# SH1_-_CONNECTORS.net
KiCad netlist of a schematic drawn in Altium Designer
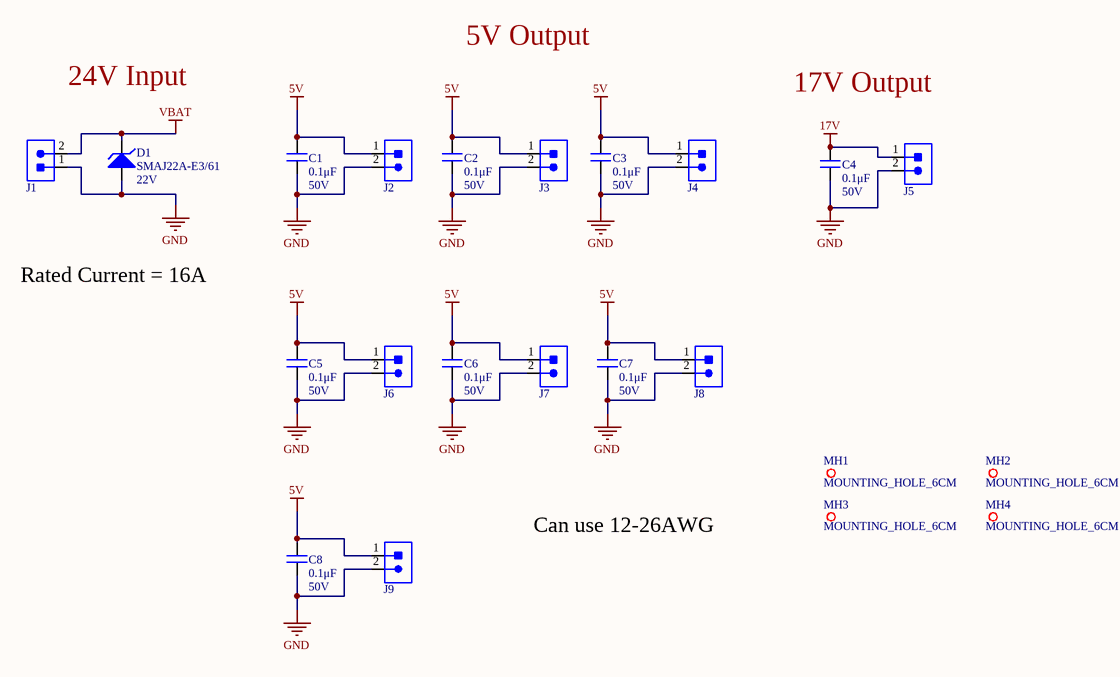
[diagram p0: SH1 - CONNECTORS.SchDoc]

(export (version "E")
  (design (tool "Eeschema 10.0.6"))
  (components
    (comp (ref "C1")
      (value "0.1μF")
      (footprint "CAPC2012X140N")
      (description "CAP CER 0.1UF 50V X7R 0805")
      (fields (field (name "TOLERANCE") "10%") (field (name "VOLTAGE RATING") "50V"))
      (libsource (lib "UWRT_Schematic_Library_2020") (part "CAP_0.1uF_50V_0805"))
    )
    (comp (ref "C2")
      (value "0.1μF")
      (footprint "CAPC2012X140N")
      (description "CAP CER 0.1UF 50V X7R 0805")
      (fields (field (name "TOLERANCE") "10%") (field (name "VOLTAGE RATING") "50V"))
      (libsource (lib "UWRT_Schematic_Library_2020") (part "CAP_0.1uF_50V_0805"))
    )
    (comp (ref "C3")
      (value "0.1μF")
      (footprint "CAPC2012X140N")
      (description "CAP CER 0.1UF 50V X7R 0805")
      (fields (field (name "TOLERANCE") "10%") (field (name "VOLTAGE RATING") "50V"))
      (libsource (lib "UWRT_Schematic_Library_2020") (part "CAP_0.1uF_50V_0805"))
    )
    (comp (ref "C4")
      (value "0.1μF")
      (footprint "CAPC2012X140N")
      (description "CAP CER 0.1UF 50V X7R 0805")
      (fields (field (name "TOLERANCE") "10%") (field (name "VOLTAGE RATING") "50V"))
      (libsource (lib "UWRT_Schematic_Library_2020") (part "CAP_0.1uF_50V_0805"))
    )
    (comp (ref "C5")
      (value "0.1μF")
      (footprint "CAPC2012X140N")
      (description "CAP CER 0.1UF 50V X7R 0805")
      (fields (field (name "TOLERANCE") "10%") (field (name "VOLTAGE RATING") "50V"))
      (libsource (lib "UWRT_Schematic_Library_2020") (part "CAP_0.1uF_50V_0805"))
    )
    (comp (ref "C6")
      (value "0.1μF")
      (footprint "CAPC2012X140N")
      (description "CAP CER 0.1UF 50V X7R 0805")
      (fields (field (name "TOLERANCE") "10%") (field (name "VOLTAGE RATING") "50V"))
      (libsource (lib "UWRT_Schematic_Library_2020") (part "CAP_0.1uF_50V_0805"))
    )
    (comp (ref "C7")
      (value "0.1μF")
      (footprint "CAPC2012X140N")
      (description "CAP CER 0.1UF 50V X7R 0805")
      (fields (field (name "TOLERANCE") "10%") (field (name "VOLTAGE RATING") "50V"))
      (libsource (lib "UWRT_Schematic_Library_2020") (part "CAP_0.1uF_50V_0805"))
    )
    (comp (ref "C8")
      (value "0.1μF")
      (footprint "CAPC2012X140N")
      (description "CAP CER 0.1UF 50V X7R 0805")
      (fields (field (name "TOLERANCE") "10%") (field (name "VOLTAGE RATING") "50V"))
      (libsource (lib "UWRT_Schematic_Library_2020") (part "CAP_0.1uF_50V_0805"))
    )
    (comp (ref "D1")
      (value "SMAJ22A-E3/61")
      (footprint "DO-214AC_UNI")
      (description "TVS DIODE 22V 35.5VC SMA")
      (fields
        (field (name "VOLTAGE") "22V")
        (field (name "MANUFACTURER PART NUMBER 1") "SMAJ22A-E3/61")
        (field (name "REVERSE STANDOFF VOLTAGE") "22V")
      )
      (libsource (lib "UWRT_Schematic_Library_2020") (part "SMAJ22A-E3/61"))
    )
    (comp (ref "J1")
      (value "1935161")
      (footprint "1935161")
      (description "TERM BLK 2POS SIDE ENTRY 5MM")
      (fields (field (name "VOLTAGE") "300V"))
      (libsource (lib "") (part "CON_2M_TERM_1"))
    )
    (comp (ref "J2")
      (value "1935161")
      (footprint "1935161")
      (description "TERM BLK 2POS SIDE ENTRY 5MM")
      (fields (field (name "VOLTAGE") "300V"))
      (libsource (lib "UWRT_Schematic_Library_2020") (part "CON_2M_TERM"))
    )
    (comp (ref "J3")
      (value "1935161")
      (footprint "1935161")
      (description "TERM BLK 2POS SIDE ENTRY 5MM")
      (fields (field (name "VOLTAGE") "300V"))
      (libsource (lib "UWRT_Schematic_Library_2020") (part "CON_2M_TERM"))
    )
    (comp (ref "J4")
      (value "1935161")
      (footprint "1935161")
      (description "TERM BLK 2POS SIDE ENTRY 5MM")
      (fields (field (name "VOLTAGE") "300V"))
      (libsource (lib "UWRT_Schematic_Library_2020") (part "CON_2M_TERM"))
    )
    (comp (ref "J5")
      (value "1935161")
      (footprint "1935161")
      (description "TERM BLK 2POS SIDE ENTRY 5MM")
      (fields (field (name "VOLTAGE") "300V"))
      (libsource (lib "UWRT_Schematic_Library_2020") (part "CON_2M_TERM"))
    )
    (comp (ref "J6")
      (value "1935161")
      (footprint "1935161")
      (description "TERM BLK 2POS SIDE ENTRY 5MM")
      (fields (field (name "VOLTAGE") "300V"))
      (libsource (lib "UWRT_Schematic_Library_2020") (part "CON_2M_TERM"))
    )
    (comp (ref "J7")
      (value "1935161")
      (footprint "1935161")
      (description "TERM BLK 2POS SIDE ENTRY 5MM")
      (fields (field (name "VOLTAGE") "300V"))
      (libsource (lib "UWRT_Schematic_Library_2020") (part "CON_2M_TERM"))
    )
    (comp (ref "J8")
      (value "1935161")
      (footprint "1935161")
      (description "TERM BLK 2POS SIDE ENTRY 5MM")
      (fields (field (name "VOLTAGE") "300V"))
      (libsource (lib "UWRT_Schematic_Library_2020") (part "CON_2M_TERM"))
    )
    (comp (ref "J9")
      (value "1935161")
      (footprint "1935161")
      (description "TERM BLK 2POS SIDE ENTRY 5MM")
      (fields (field (name "VOLTAGE") "300V"))
      (libsource (lib "UWRT_Schematic_Library_2020") (part "CON_2M_TERM"))
    )
    (comp (ref "MH1")
      (value "MOUNTING_HOLE_6CM")
      (footprint "MOUNTING_HOLE")
      (libsource (lib "UWRT_Schematic_Library_2020") (part "MOUNTING_HOLE_6CM"))
    )
    (comp (ref "MH2")
      (value "MOUNTING_HOLE_6CM")
      (footprint "MOUNTING_HOLE")
      (libsource (lib "UWRT_Schematic_Library_2020") (part "MOUNTING_HOLE_6CM"))
    )
    (comp (ref "MH3")
      (value "MOUNTING_HOLE_6CM")
      (footprint "MOUNTING_HOLE")
      (libsource (lib "UWRT_Schematic_Library_2020") (part "MOUNTING_HOLE_6CM"))
    )
    (comp (ref "MH4")
      (value "MOUNTING_HOLE_6CM")
      (footprint "MOUNTING_HOLE")
      (libsource (lib "UWRT_Schematic_Library_2020") (part "MOUNTING_HOLE_6CM"))
    )
  )
  (nets
    (net (code "1") (name "5V") (class "Default")
      (node (ref "C1") (pin "2") (pinfunction "2_2") (pintype "passive"))
      (node (ref "C2") (pin "2") (pinfunction "2_2") (pintype "passive"))
      (node (ref "C3") (pin "2") (pinfunction "2_2") (pintype "passive"))
      (node (ref "C5") (pin "2") (pinfunction "2_2") (pintype "passive"))
      (node (ref "C6") (pin "2") (pinfunction "2_2") (pintype "passive"))
      (node (ref "C7") (pin "2") (pinfunction "2_2") (pintype "passive"))
      (node (ref "C8") (pin "2") (pinfunction "2_2") (pintype "passive"))
      (node (ref "J2") (pin "1") (pinfunction "1_1") (pintype "passive"))
      (node (ref "J3") (pin "1") (pinfunction "1_1") (pintype "passive"))
      (node (ref "J4") (pin "1") (pinfunction "1_1") (pintype "passive"))
      (node (ref "J6") (pin "1") (pinfunction "1_1") (pintype "passive"))
      (node (ref "J7") (pin "1") (pinfunction "1_1") (pintype "passive"))
      (node (ref "J8") (pin "1") (pinfunction "1_1") (pintype "passive"))
      (node (ref "J9") (pin "1") (pinfunction "1_1") (pintype "passive"))
    )
    (net (code "2") (name "17V") (class "Default")
      (node (ref "C4") (pin "2") (pinfunction "2_2") (pintype "passive"))
      (node (ref "J5") (pin "1") (pinfunction "1_1") (pintype "passive"))
    )
    (net (code "3") (name "GND") (class "Default")
      (node (ref "C1") (pin "1") (pinfunction "1_1") (pintype "passive"))
      (node (ref "C2") (pin "1") (pinfunction "1_1") (pintype "passive"))
      (node (ref "C3") (pin "1") (pinfunction "1_1") (pintype "passive"))
      (node (ref "C4") (pin "1") (pinfunction "1_1") (pintype "passive"))
      (node (ref "C5") (pin "1") (pinfunction "1_1") (pintype "passive"))
      (node (ref "C6") (pin "1") (pinfunction "1_1") (pintype "passive"))
      (node (ref "C7") (pin "1") (pinfunction "1_1") (pintype "passive"))
      (node (ref "C8") (pin "1") (pinfunction "1_1") (pintype "passive"))
      (node (ref "D1") (pin "1") (pinfunction "1_1") (pintype "passive"))
      (node (ref "J1") (pin "1") (pinfunction "1_1") (pintype "passive"))
      (node (ref "J2") (pin "2") (pinfunction "2_2") (pintype "passive"))
      (node (ref "J3") (pin "2") (pinfunction "2_2") (pintype "passive"))
      (node (ref "J4") (pin "2") (pinfunction "2_2") (pintype "passive"))
      (node (ref "J5") (pin "2") (pinfunction "2_2") (pintype "passive"))
      (node (ref "J6") (pin "2") (pinfunction "2_2") (pintype "passive"))
      (node (ref "J7") (pin "2") (pinfunction "2_2") (pintype "passive"))
      (node (ref "J8") (pin "2") (pinfunction "2_2") (pintype "passive"))
      (node (ref "J9") (pin "2") (pinfunction "2_2") (pintype "passive"))
    )
    (net (code "4") (name "VBAT") (class "Default")
      (node (ref "D1") (pin "2") (pinfunction "2_2") (pintype "passive"))
      (node (ref "J1") (pin "2") (pinfunction "2_2") (pintype "passive"))
    )
  )
)
